# MCU.net
KiCad netlist of a schematic drawn in Altium Designer
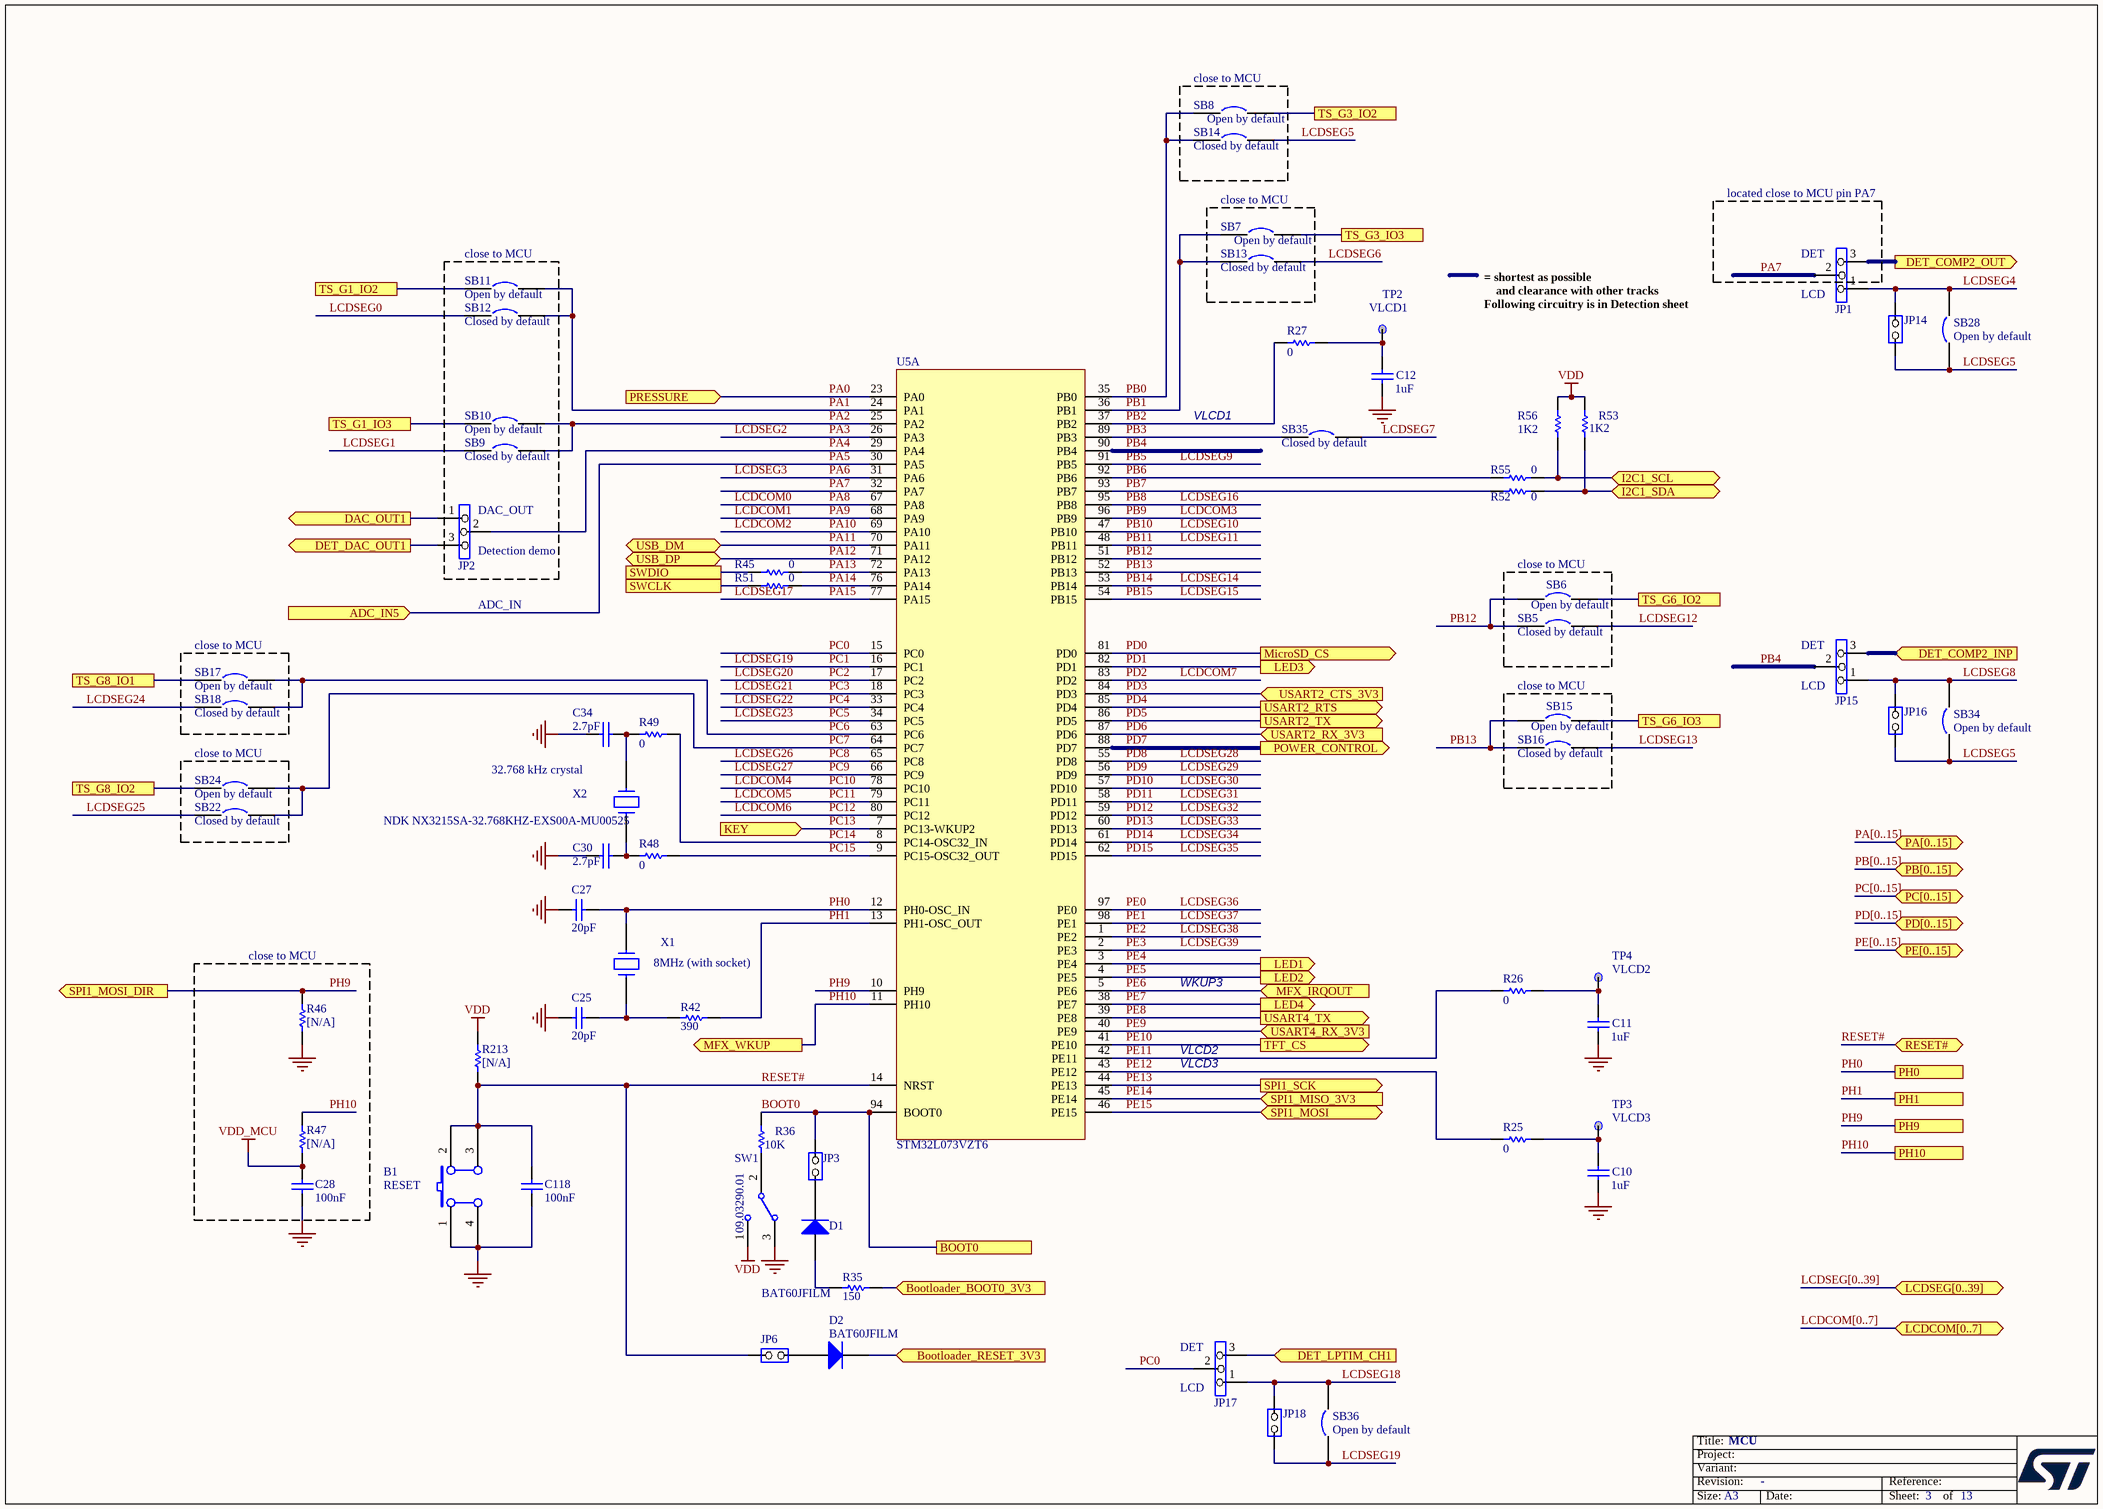
[diagram p0: MCU.SchDoc]

(export (version "E")
  (design (tool "Eeschema 10.0.6"))
  (components
    (comp (ref "B1")
      (value "RESET")
      (footprint "PB10")
      (description "SE PUSHBUTTON")
      (libsource (lib "Documents") (part "SW PUSHBUTTON"))
    )
    (comp (ref "C10")
      (value "1uF")
      (footprint "0603C")
      (description "Capacitor")
      (fields (field (name "PUBLISHER") "Altium Limited"))
      (libsource (lib "Miscellaneous Devices") (part "CAP"))
    )
    (comp (ref "C11")
      (value "1uF")
      (footprint "0603C")
      (description "Capacitor")
      (fields (field (name "PUBLISHER") "Altium Limited"))
      (libsource (lib "Miscellaneous Devices") (part "CAP"))
    )
    (comp (ref "C12")
      (value "1uF")
      (footprint "0603C")
      (description "Capacitor")
      (fields (field (name "PUBLISHER") "Altium Limited"))
      (libsource (lib "Miscellaneous Devices") (part "CAP"))
    )
    (comp (ref "C25")
      (value "20pF")
      (footprint "0402C")
      (description "Capacitor")
      (fields (field (name "PUBLISHER") "Altium Limited"))
      (libsource (lib "Miscellaneous Devices") (part "CAP"))
    )
    (comp (ref "C27")
      (value "20pF")
      (footprint "0402C")
      (description "Capacitor")
      (fields (field (name "PUBLISHER") "Altium Limited"))
      (libsource (lib "Miscellaneous Devices") (part "CAP"))
    )
    (comp (ref "C28")
      (value "100nF")
      (footprint "0402C")
      (description "Capacitor")
      (fields (field (name "PUBLISHER") "Altium Limited"))
      (libsource (lib "Miscellaneous Devices") (part "CAP"))
    )
    (comp (ref "C30")
      (value "2.7pF")
      (footprint "0603C")
      (description "Capacitor")
      (libsource (lib "*") (part "CAP"))
    )
    (comp (ref "C34")
      (value "2.7pF")
      (footprint "0603C")
      (description "Capacitor")
      (libsource (lib "*") (part "CAP"))
    )
    (comp (ref "C118")
      (value "100nF")
      (footprint "0402C")
      (description "Capacitor")
      (fields (field (name "PUBLISHER") "Altium Limited"))
      (libsource (lib "Miscellaneous Devices") (part "CAP"))
    )
    (comp (ref "D1")
      (value "BAT60JFILM")
      (footprint "SOD-323")
      (description "Default Diode")
      (fields (field (name "PUBLISHER") "Altium Limited"))
      (libsource (lib "Miscellaneous Devices") (part "Diode"))
    )
    (comp (ref "D2")
      (value "BAT60JFILM")
      (footprint "SOD-323")
      (description "Default Diode")
      (fields (field (name "PUBLISHER") "Altium Limited"))
      (libsource (lib "Miscellaneous Devices") (part "Diode"))
    )
    (comp (ref "JP1") (value "~") (footprint "SIP3") (libsource (lib "STR910_SCHLIB") (part "Jumper3")))
    (comp (ref "JP2") (value "~") (footprint "SIP3") (libsource (lib "STR910_SCHLIB") (part "Jumper3")))
    (comp (ref "JP3") (value "~") (footprint "SIP2") (libsource (lib "*") (part "JP2")))
    (comp (ref "JP6") (value "~") (footprint "SIP2") (libsource (lib "*") (part "JP2")))
    (comp (ref "JP14") (value "~") (footprint "SIP2") (libsource (lib "*") (part "JP2")))
    (comp (ref "JP15") (value "~") (footprint "SIP3") (libsource (lib "STR910_SCHLIB") (part "Jumper3")))
    (comp (ref "JP16") (value "~") (footprint "SIP2") (libsource (lib "*") (part "JP2")))
    (comp (ref "JP17") (value "~") (footprint "SIP3") (libsource (lib "STR910_SCHLIB") (part "Jumper3")))
    (comp (ref "JP18") (value "~") (footprint "SIP2") (libsource (lib "*") (part "JP2")))
    (comp (ref "R25")
      (value "0")
      (footprint "0603R")
      (description "Resistor")
      (fields (field (name "PUBLISHER") "Altium Limited"))
      (libsource (lib "Miscellaneous Devices") (part "Res1"))
    )
    (comp (ref "R26")
      (value "0")
      (footprint "0603R")
      (description "Resistor")
      (fields (field (name "PUBLISHER") "Altium Limited"))
      (libsource (lib "Miscellaneous Devices") (part "Res1"))
    )
    (comp (ref "R27")
      (value "0")
      (footprint "0603R")
      (description "Resistor")
      (fields (field (name "PUBLISHER") "Altium Limited"))
      (libsource (lib "Miscellaneous Devices") (part "Res1"))
    )
    (comp (ref "R35")
      (value "150")
      (footprint "0402R")
      (description "Resistor")
      (fields (field (name "PUBLISHER") "Altium Limited"))
      (libsource (lib "Miscellaneous Devices") (part "res1"))
    )
    (comp (ref "R36")
      (value "10K")
      (footprint "0402R")
      (description "Resistor")
      (fields (field (name "PUBLISHER") "Altium Limited"))
      (libsource (lib "Miscellaneous Devices") (part "res1"))
    )
    (comp (ref "R42")
      (value "390")
      (footprint "0603R")
      (description "Resistor")
      (fields (field (name "PUBLISHER") "Altium Limited"))
      (libsource (lib "Miscellaneous Devices") (part "Res1"))
    )
    (comp (ref "R45")
      (value "0")
      (footprint "0603R")
      (description "Resistor")
      (fields (field (name "PUBLISHER") "Altium Limited"))
      (libsource (lib "Miscellaneous Devices") (part "Res1"))
    )
    (comp (ref "R46")
      (value "[N/A]")
      (footprint "0603R")
      (description "Resistor")
      (fields (field (name "PUBLISHER") "Altium Limited"))
      (libsource (lib "Miscellaneous Devices") (part "res1"))
    )
    (comp (ref "R47")
      (value "[N/A]")
      (footprint "0603R")
      (description "Resistor")
      (fields (field (name "PUBLISHER") "Altium Limited"))
      (libsource (lib "Miscellaneous Devices") (part "res1"))
    )
    (comp (ref "R48")
      (value "0")
      (footprint "0603R")
      (description "Resistor")
      (fields (field (name "PUBLISHER") "Altium Limited"))
      (libsource (lib "") (part "Res1_1"))
    )
    (comp (ref "R49")
      (value "0")
      (footprint "0603R")
      (description "Resistor")
      (fields (field (name "PUBLISHER") "Altium Limited"))
      (libsource (lib "") (part "Res1_1"))
    )
    (comp (ref "R51")
      (value "0")
      (footprint "0603R")
      (description "Resistor")
      (fields (field (name "PUBLISHER") "Altium Limited"))
      (libsource (lib "Miscellaneous Devices") (part "Res1"))
    )
    (comp (ref "R52")
      (value "0")
      (footprint "0603R")
      (description "Resistor")
      (fields (field (name "PUBLISHER") "Altium Limited"))
      (libsource (lib "Miscellaneous Devices") (part "Res1"))
    )
    (comp (ref "R53")
      (value "1K2")
      (footprint "0603R")
      (description "Resistor")
      (fields (field (name "PUBLISHER") "Altium Limited"))
      (libsource (lib "Miscellaneous Devices") (part "Res1"))
    )
    (comp (ref "R55")
      (value "0")
      (footprint "0603R")
      (description "Resistor")
      (fields (field (name "PUBLISHER") "Altium Limited"))
      (libsource (lib "Miscellaneous Devices") (part "Res1"))
    )
    (comp (ref "R56")
      (value "1K2")
      (footprint "0603R")
      (description "Resistor")
      (fields (field (name "PUBLISHER") "Altium Limited"))
      (libsource (lib "Miscellaneous Devices") (part "Res1"))
    )
    (comp (ref "R213")
      (value "[N/A]")
      (footprint "0603R")
      (description "Resistor")
      (fields (field (name "PUBLISHER") "Altium Limited"))
      (libsource (lib "Miscellaneous Devices") (part "res1"))
    )
    (comp (ref "SB5")
      (value "Closed by default")
      (footprint "SB_0603")
      (description "Circuit Breaker")
      (fields (field (name "PUBLISHER") "Altium Limited"))
      (libsource (lib "Miscellaneous Devices") (part "Circuit Breaker"))
    )
    (comp (ref "SB6")
      (value "Open by default")
      (footprint "SB_0603")
      (description "Circuit Breaker")
      (fields (field (name "PUBLISHER") "Altium Limited"))
      (libsource (lib "Miscellaneous Devices") (part "Circuit Breaker"))
    )
    (comp (ref "SB7")
      (value "Open by default")
      (footprint "SB_0603")
      (description "Circuit Breaker")
      (fields (field (name "PUBLISHER") "Altium Limited"))
      (libsource (lib "Miscellaneous Devices") (part "Circuit Breaker"))
    )
    (comp (ref "SB8")
      (value "Open by default")
      (footprint "SB_0603")
      (description "Circuit Breaker")
      (fields (field (name "PUBLISHER") "Altium Limited"))
      (libsource (lib "Miscellaneous Devices") (part "Circuit Breaker"))
    )
    (comp (ref "SB9")
      (value "Closed by default")
      (footprint "SB_0603")
      (description "Circuit Breaker")
      (fields (field (name "PUBLISHER") "Altium Limited"))
      (libsource (lib "Miscellaneous Devices") (part "Circuit Breaker"))
    )
    (comp (ref "SB10")
      (value "Open by default")
      (footprint "SB_0603")
      (description "Circuit Breaker")
      (fields (field (name "PUBLISHER") "Altium Limited"))
      (libsource (lib "Miscellaneous Devices") (part "Circuit Breaker"))
    )
    (comp (ref "SB11")
      (value "Open by default")
      (footprint "SB_0603")
      (description "Circuit Breaker")
      (fields (field (name "PUBLISHER") "Altium Limited"))
      (libsource (lib "Miscellaneous Devices") (part "Circuit Breaker"))
    )
    (comp (ref "SB12")
      (value "Closed by default")
      (footprint "SB_0603")
      (description "Circuit Breaker")
      (fields (field (name "PUBLISHER") "Altium Limited"))
      (libsource (lib "Miscellaneous Devices") (part "Circuit Breaker"))
    )
    (comp (ref "SB13")
      (value "Closed by default")
      (footprint "SB_0603")
      (description "Circuit Breaker")
      (fields (field (name "PUBLISHER") "Altium Limited"))
      (libsource (lib "Miscellaneous Devices") (part "Circuit Breaker"))
    )
    (comp (ref "SB14")
      (value "Closed by default")
      (footprint "SB_0603")
      (description "Circuit Breaker")
      (fields (field (name "PUBLISHER") "Altium Limited"))
      (libsource (lib "Miscellaneous Devices") (part "Circuit Breaker"))
    )
    (comp (ref "SB15")
      (value "Open by default")
      (footprint "SB_0603")
      (description "Circuit Breaker")
      (fields (field (name "PUBLISHER") "Altium Limited"))
      (libsource (lib "Miscellaneous Devices") (part "Circuit Breaker"))
    )
    (comp (ref "SB16")
      (value "Closed by default")
      (footprint "SB_0603")
      (description "Circuit Breaker")
      (fields (field (name "PUBLISHER") "Altium Limited"))
      (libsource (lib "Miscellaneous Devices") (part "Circuit Breaker"))
    )
    (comp (ref "SB17")
      (value "Open by default")
      (footprint "SB_0603")
      (description "Circuit Breaker")
      (fields (field (name "PUBLISHER") "Altium Limited"))
      (libsource (lib "Miscellaneous Devices") (part "Circuit Breaker"))
    )
    (comp (ref "SB18")
      (value "Closed by default")
      (footprint "SB_0603")
      (description "Circuit Breaker")
      (fields (field (name "PUBLISHER") "Altium Limited"))
      (libsource (lib "Miscellaneous Devices") (part "Circuit Breaker"))
    )
    (comp (ref "SB22")
      (value "Closed by default")
      (footprint "SB_0603")
      (description "Circuit Breaker")
      (fields (field (name "PUBLISHER") "Altium Limited"))
      (libsource (lib "Miscellaneous Devices") (part "Circuit Breaker"))
    )
    (comp (ref "SB24")
      (value "Open by default")
      (footprint "SB_0603")
      (description "Circuit Breaker")
      (fields (field (name "PUBLISHER") "Altium Limited"))
      (libsource (lib "Miscellaneous Devices") (part "Circuit Breaker"))
    )
    (comp (ref "SB28")
      (value "Open by default")
      (footprint "SB_0603")
      (description "Circuit Breaker")
      (fields (field (name "PUBLISHER") "Altium Limited"))
      (libsource (lib "Miscellaneous Devices") (part "Circuit Breaker"))
    )
    (comp (ref "SB34")
      (value "Open by default")
      (footprint "SB_0603")
      (description "Circuit Breaker")
      (fields (field (name "PUBLISHER") "Altium Limited"))
      (libsource (lib "Miscellaneous Devices") (part "Circuit Breaker"))
    )
    (comp (ref "SB35")
      (value "Closed by default")
      (footprint "SB_0603")
      (description "Circuit Breaker")
      (fields (field (name "PUBLISHER") "Altium Limited"))
      (libsource (lib "Miscellaneous Devices") (part "Circuit Breaker"))
    )
    (comp (ref "SB36")
      (value "Open by default")
      (footprint "SB_0603")
      (description "Circuit Breaker")
      (fields (field (name "PUBLISHER") "Altium Limited"))
      (libsource (lib "Miscellaneous Devices") (part "Circuit Breaker"))
    )
    (comp (ref "SW1")
      (value "09.03290.01")
      (footprint "SW1_3TH_2R54_10X2R5")
      (description "SPDT Subminiature Toggle Switch, Right Angle Mounting, Vertical Actuation")
      (fields (field (name "PUBLISHER") "Altium Limited"))
      (libsource (lib "Miscellaneous Devices") (part "SW-SPDT"))
    )
    (comp (ref "TP2")
      (value "TP")
      (footprint "TP")
      (fields (field (name "SILKSCREEN") "VLCD1"))
      (libsource (lib "*") (part "TP"))
    )
    (comp (ref "TP3")
      (value "TP")
      (footprint "TP")
      (fields (field (name "SILKSCREEN") "VLCD3"))
      (libsource (lib "*") (part "TP"))
    )
    (comp (ref "TP4")
      (value "TP")
      (footprint "TP")
      (fields (field (name "SILKSCREEN") "VLCD2"))
      (libsource (lib "*") (part "TP"))
    )
    (comp (ref "U5")
      (value "STM32L073VZT6")
      (footprint "IC149_100_025_B5")
      (libsource (lib "Almos") (part "BigNemo"))
    )
    (comp (ref "X1")
      (value "8MHz (with socket)")
      (footprint "XTAL_SOCKET")
      (description "Crystal")
      (libsource (lib "*") (part "CRYSTAL"))
    )
    (comp (ref "X2")
      (value "NDK NX3215SA-32.768KHZ-EXS00A-MU00525")
      (footprint "XTAL_2SM_3R2X1R5")
      (description "Crystal")
      (libsource (lib "MB1167") (part "CRYSTAL_32K"))
    )
  )
  (nets
    (net (code "1") (name "/BOOT0") (class "Default")
      (node (ref "JP3") (pin "1") (pinfunction "COMMON_1") (pintype "passive"))
      (node (ref "R36") (pin "1") (pinfunction "1_1") (pintype "passive"))
      (node (ref "U5") (pin "94") (pinfunction "BOOT0_94") (pintype "passive"))
    )
    (net (code "2") (name "/Bootloader_BOOT0_3V3") (class "Default")
      (node (ref "R35") (pin "2") (pinfunction "2_2") (pintype "passive"))
    )
    (net (code "3") (name "/Bootloader_RESET_3V3") (class "Default")
      (node (ref "D2") (pin "2") (pinfunction "K_2") (pintype "passive"))
    )
    (net (code "4") (name "/DAC_OUT1") (class "Default") (node (ref "JP2") (pin "1") (pintype "passive")))
    (net (code "5") (name "/DET_COMP2_INP") (class "Default")
      (node (ref "JP15") (pin "3") (pintype "passive"))
    )
    (net (code "6") (name "/DET_COMP2_OUT") (class "Default")
      (node (ref "JP1") (pin "3") (pintype "passive"))
    )
    (net (code "7") (name "/DET_DAC_OUT1") (class "Default") (node (ref "JP2") (pin "3") (pintype "passive")))
    (net (code "8") (name "/DET_LPTIM_CH1") (class "Default")
      (node (ref "JP17") (pin "3") (pintype "passive"))
    )
    (net (code "9") (name "/I2C1_SCL") (class "Default")
      (node (ref "R55") (pin "2") (pinfunction "2_2") (pintype "passive"))
      (node (ref "R56") (pin "1") (pinfunction "1_1") (pintype "passive"))
    )
    (net (code "10") (name "/I2C1_SDA") (class "Default")
      (node (ref "R52") (pin "2") (pinfunction "2_2") (pintype "passive"))
      (node (ref "R53") (pin "1") (pinfunction "1_1") (pintype "passive"))
    )
    (net (code "12") (name "/LCDSEG0") (class "Default")
      (node (ref "SB12") (pin "1") (pinfunction "1_1") (pintype "passive"))
    )
    (net (code "13") (name "/LCDSEG1") (class "Default")
      (node (ref "SB9") (pin "1") (pinfunction "1_1") (pintype "passive"))
    )
    (net (code "14") (name "/LCDSEG4") (class "Default")
      (node (ref "JP1") (pin "1") (pintype "passive"))
      (node (ref "JP14") (pin "2") (pinfunction "NO_2") (pintype "passive"))
      (node (ref "SB28") (pin "2") (pinfunction "2_2") (pintype "passive"))
    )
    (net (code "15") (name "/LCDSEG5") (class "Default")
      (node (ref "JP14") (pin "1") (pinfunction "COMMON_1") (pintype "passive"))
      (node (ref "JP16") (pin "1") (pinfunction "COMMON_1") (pintype "passive"))
      (node (ref "SB14") (pin "2") (pinfunction "2_2") (pintype "passive"))
      (node (ref "SB28") (pin "1") (pinfunction "1_1") (pintype "passive"))
      (node (ref "SB34") (pin "1") (pinfunction "1_1") (pintype "passive"))
    )
    (net (code "16") (name "/LCDSEG6") (class "Default")
      (node (ref "SB13") (pin "2") (pinfunction "2_2") (pintype "passive"))
    )
    (net (code "17") (name "/LCDSEG7") (class "Default")
      (node (ref "SB35") (pin "2") (pinfunction "2_2") (pintype "passive"))
    )
    (net (code "18") (name "/LCDSEG8") (class "Default")
      (node (ref "JP15") (pin "1") (pintype "passive"))
      (node (ref "JP16") (pin "2") (pinfunction "NO_2") (pintype "passive"))
      (node (ref "SB34") (pin "2") (pinfunction "2_2") (pintype "passive"))
    )
    (net (code "19") (name "/LCDSEG12") (class "Default")
      (node (ref "SB5") (pin "2") (pinfunction "2_2") (pintype "passive"))
    )
    (net (code "20") (name "/LCDSEG13") (class "Default")
      (node (ref "SB16") (pin "2") (pinfunction "2_2") (pintype "passive"))
    )
    (net (code "21") (name "/LCDSEG18") (class "Default")
      (node (ref "JP17") (pin "1") (pintype "passive"))
      (node (ref "JP18") (pin "2") (pinfunction "NO_2") (pintype "passive"))
      (node (ref "SB36") (pin "2") (pinfunction "2_2") (pintype "passive"))
    )
    (net (code "22") (name "/LCDSEG24") (class "Default")
      (node (ref "SB18") (pin "1") (pinfunction "1_1") (pintype "passive"))
    )
    (net (code "23") (name "/LCDSEG25") (class "Default")
      (node (ref "SB22") (pin "1") (pinfunction "1_1") (pintype "passive"))
    )
    (net (code "25") (name "/PA0") (class "Default")
      (node (ref "U5") (pin "23") (pinfunction "PA0_23") (pintype "passive"))
    )
    (net (code "26") (name "/PA1") (class "Default")
      (node (ref "SB11") (pin "2") (pinfunction "2_2") (pintype "passive"))
      (node (ref "SB12") (pin "2") (pinfunction "2_2") (pintype "passive"))
      (node (ref "U5") (pin "24") (pinfunction "PA1_24") (pintype "passive"))
    )
    (net (code "27") (name "/PA2") (class "Default")
      (node (ref "SB10") (pin "2") (pinfunction "2_2") (pintype "passive"))
      (node (ref "SB9") (pin "2") (pinfunction "2_2") (pintype "passive"))
      (node (ref "U5") (pin "25") (pinfunction "PA2_25") (pintype "passive"))
    )
    (net (code "28") (name "/PA3") (class "Default")
      (node (ref "U5") (pin "26") (pinfunction "PA3_26") (pintype "passive"))
    )
    (net (code "29") (name "/PA4") (class "Default")
      (node (ref "JP2") (pin "2") (pintype "passive"))
      (node (ref "U5") (pin "29") (pinfunction "PA4_29") (pintype "passive"))
    )
    (net (code "30") (name "/PA5") (class "Default")
      (node (ref "U5") (pin "30") (pinfunction "PA5_30") (pintype "passive"))
    )
    (net (code "31") (name "/PA6") (class "Default")
      (node (ref "U5") (pin "31") (pinfunction "PA6_31") (pintype "passive"))
    )
    (net (code "32") (name "/PA7") (class "Default")
      (node (ref "JP1") (pin "2") (pintype "passive"))
      (node (ref "U5") (pin "32") (pinfunction "PA7_32") (pintype "passive"))
    )
    (net (code "33") (name "/PA8") (class "Default")
      (node (ref "U5") (pin "67") (pinfunction "PA8_67") (pintype "passive"))
    )
    (net (code "34") (name "/PA9") (class "Default")
      (node (ref "U5") (pin "68") (pinfunction "PA9_68") (pintype "passive"))
    )
    (net (code "35") (name "/PA10") (class "Default")
      (node (ref "U5") (pin "69") (pinfunction "PA10_69") (pintype "passive"))
    )
    (net (code "36") (name "/PA11") (class "Default")
      (node (ref "U5") (pin "70") (pinfunction "PA11_70") (pintype "passive"))
    )
    (net (code "37") (name "/PA12") (class "Default")
      (node (ref "U5") (pin "71") (pinfunction "PA12_71") (pintype "passive"))
    )
    (net (code "38") (name "/PA13") (class "Default")
      (node (ref "R45") (pin "2") (pinfunction "2_2") (pintype "passive"))
      (node (ref "U5") (pin "72") (pinfunction "PA13_72") (pintype "passive"))
    )
    (net (code "39") (name "/PA14") (class "Default")
      (node (ref "R51") (pin "2") (pinfunction "2_2") (pintype "passive"))
      (node (ref "U5") (pin "76") (pinfunction "PA14_76") (pintype "passive"))
    )
    (net (code "40") (name "/PA15") (class "Default")
      (node (ref "U5") (pin "77") (pinfunction "PA15_77") (pintype "passive"))
    )
    (net (code "42") (name "/PB0") (class "Default")
      (node (ref "SB14") (pin "1") (pinfunction "1_1") (pintype "passive"))
      (node (ref "SB8") (pin "1") (pinfunction "1_1") (pintype "passive"))
      (node (ref "U5") (pin "35") (pinfunction "PB0_35") (pintype "passive"))
    )
    (net (code "43") (name "/PB1") (class "Default")
      (node (ref "SB13") (pin "1") (pinfunction "1_1") (pintype "passive"))
      (node (ref "SB7") (pin "1") (pinfunction "1_1") (pintype "passive"))
      (node (ref "U5") (pin "36") (pinfunction "PB1_36") (pintype "passive"))
    )
    (net (code "44") (name "/PB2") (class "Default")
      (node (ref "R27") (pin "1") (pinfunction "1_1") (pintype "passive"))
      (node (ref "U5") (pin "37") (pinfunction "PB2_37") (pintype "passive"))
    )
    (net (code "45") (name "/PB3") (class "Default")
      (node (ref "SB35") (pin "1") (pinfunction "1_1") (pintype "passive"))
      (node (ref "U5") (pin "89") (pinfunction "PB3_89") (pintype "passive"))
    )
    (net (code "46") (name "/PB4") (class "Default")
      (node (ref "JP15") (pin "2") (pintype "passive"))
      (node (ref "U5") (pin "90") (pinfunction "PB4_90") (pintype "passive"))
    )
    (net (code "47") (name "/PB5") (class "Default")
      (node (ref "U5") (pin "91") (pinfunction "PB5_91") (pintype "passive"))
    )
    (net (code "48") (name "/PB6") (class "Default")
      (node (ref "R55") (pin "1") (pinfunction "1_1") (pintype "passive"))
      (node (ref "U5") (pin "92") (pinfunction "PB6_92") (pintype "passive"))
    )
    (net (code "49") (name "/PB7") (class "Default")
      (node (ref "R52") (pin "1") (pinfunction "1_1") (pintype "passive"))
      (node (ref "U5") (pin "93") (pinfunction "PB7_93") (pintype "passive"))
    )
    (net (code "50") (name "/PB8") (class "Default")
      (node (ref "U5") (pin "95") (pinfunction "PB8_95") (pintype "passive"))
    )
    (net (code "51") (name "/PB9") (class "Default")
      (node (ref "U5") (pin "96") (pinfunction "PB9_96") (pintype "passive"))
    )
    (net (code "52") (name "/PB10") (class "Default")
      (node (ref "U5") (pin "47") (pinfunction "PB10_47") (pintype "passive"))
    )
    (net (code "53") (name "/PB11") (class "Default")
      (node (ref "U5") (pin "48") (pinfunction "PB11_48") (pintype "passive"))
    )
    (net (code "54") (name "/PB12") (class "Default")
      (node (ref "SB5") (pin "1") (pinfunction "1_1") (pintype "passive"))
      (node (ref "SB6") (pin "1") (pinfunction "1_1") (pintype "passive"))
      (node (ref "U5") (pin "51") (pinfunction "PB12_51") (pintype "passive"))
    )
    (net (code "55") (name "/PB13") (class "Default")
      (node (ref "SB15") (pin "1") (pinfunction "1_1") (pintype "passive"))
      (node (ref "SB16") (pin "1") (pinfunction "1_1") (pintype "passive"))
      (node (ref "U5") (pin "52") (pinfunction "PB13_52") (pintype "passive"))
    )
    (net (code "56") (name "/PB14") (class "Default")
      (node (ref "U5") (pin "53") (pinfunction "PB14_53") (pintype "passive"))
    )
    (net (code "57") (name "/PB15") (class "Default")
      (node (ref "U5") (pin "54") (pinfunction "PB15_54") (pintype "passive"))
    )
    (net (code "59") (name "/PC0") (class "Default")
      (node (ref "JP17") (pin "2") (pintype "passive"))
      (node (ref "U5") (pin "15") (pinfunction "PC0_15") (pintype "passive"))
    )
    (net (code "60") (name "/PC1") (class "Default")
      (node (ref "JP18") (pin "1") (pinfunction "COMMON_1") (pintype "passive"))
      (node (ref "SB36") (pin "1") (pinfunction "1_1") (pintype "passive"))
      (node (ref "U5") (pin "16") (pinfunction "PC1_16") (pintype "passive"))
    )
    (net (code "61") (name "/PC2") (class "Default")
      (node (ref "U5") (pin "17") (pinfunction "PC2_17") (pintype "passive"))
    )
    (net (code "62") (name "/PC3") (class "Default")
      (node (ref "U5") (pin "18") (pinfunction "PC3_18") (pintype "passive"))
    )
    (net (code "63") (name "/PC4") (class "Default")
      (node (ref "U5") (pin "33") (pinfunction "PC4_33") (pintype "passive"))
    )
    (net (code "64") (name "/PC5") (class "Default")
      (node (ref "U5") (pin "34") (pinfunction "PC5_34") (pintype "passive"))
    )
    (net (code "65") (name "/PC6") (class "Default")
      (node (ref "SB17") (pin "2") (pinfunction "2_2") (pintype "passive"))
      (node (ref "SB18") (pin "2") (pinfunction "2_2") (pintype "passive"))
      (node (ref "U5") (pin "63") (pinfunction "PC6_63") (pintype "passive"))
    )
    (net (code "66") (name "/PC7") (class "Default")
      (node (ref "SB22") (pin "2") (pinfunction "2_2") (pintype "passive"))
      (node (ref "SB24") (pin "2") (pinfunction "2_2") (pintype "passive"))
      (node (ref "U5") (pin "64") (pinfunction "PC7_64") (pintype "passive"))
    )
    (net (code "67") (name "/PC8") (class "Default")
      (node (ref "U5") (pin "65") (pinfunction "PC8_65") (pintype "passive"))
    )
    (net (code "68") (name "/PC9") (class "Default")
      (node (ref "U5") (pin "66") (pinfunction "PC9_66") (pintype "passive"))
    )
    (net (code "69") (name "/PC10") (class "Default")
      (node (ref "U5") (pin "78") (pinfunction "PC10_78") (pintype "passive"))
    )
    (net (code "70") (name "/PC11") (class "Default")
      (node (ref "U5") (pin "79") (pinfunction "PC11_79") (pintype "passive"))
    )
    (net (code "71") (name "/PC12") (class "Default")
      (node (ref "U5") (pin "80") (pinfunction "PC12_80") (pintype "passive"))
    )
    (net (code "72") (name "/PC13") (class "Default")
      (node (ref "U5") (pin "7") (pinfunction "PC13-WKUP2_7") (pintype "passive"))
    )
    (net (code "73") (name "/PC14") (class "Default")
      (node (ref "R49") (pin "2") (pinfunction "2_2") (pintype "passive"))
      (node (ref "U5") (pin "8") (pinfunction "PC14-OSC32_IN_8") (pintype "passive"))
    )
    (net (code "74") (name "/PC15") (class "Default")
      (node (ref "R48") (pin "2") (pinfunction "2_2") (pintype "passive"))
      (node (ref "U5") (pin "9") (pinfunction "PC15-OSC32_OUT_9") (pintype "passive"))
    )
    (net (code "76") (name "/PD0") (class "Default")
      (node (ref "U5") (pin "81") (pinfunction "PD0_81") (pintype "passive"))
    )
    (net (code "77") (name "/PD1") (class "Default")
      (node (ref "U5") (pin "82") (pinfunction "PD1_82") (pintype "passive"))
    )
    (net (code "78") (name "/PD2") (class "Default")
      (node (ref "U5") (pin "83") (pinfunction "PD2_83") (pintype "passive"))
    )
    (net (code "79") (name "/PD3") (class "Default")
      (node (ref "U5") (pin "84") (pinfunction "PD3_84") (pintype "passive"))
    )
    (net (code "80") (name "/PD4") (class "Default")
      (node (ref "U5") (pin "85") (pinfunction "PD4_85") (pintype "passive"))
    )
    (net (code "81") (name "/PD5") (class "Default")
      (node (ref "U5") (pin "86") (pinfunction "PD5_86") (pintype "passive"))
    )
    (net (code "82") (name "/PD6") (class "Default")
      (node (ref "U5") (pin "87") (pinfunction "PD6_87") (pintype "passive"))
    )
    (net (code "83") (name "/PD7") (class "Default")
      (node (ref "U5") (pin "88") (pinfunction "PD7_88") (pintype "passive"))
    )
    (net (code "84") (name "/PD8") (class "Default")
      (node (ref "U5") (pin "55") (pinfunction "PD8_55") (pintype "passive"))
    )
    (net (code "85") (name "/PD9") (class "Default")
      (node (ref "U5") (pin "56") (pinfunction "PD9_56") (pintype "passive"))
    )
    (net (code "86") (name "/PD10") (class "Default")
      (node (ref "U5") (pin "57") (pinfunction "PD10_57") (pintype "passive"))
    )
    (net (code "87") (name "/PD11") (class "Default")
      (node (ref "U5") (pin "58") (pinfunction "PD11_58") (pintype "passive"))
    )
    (net (code "88") (name "/PD12") (class "Default")
      (node (ref "U5") (pin "59") (pinfunction "PD12_59") (pintype "passive"))
    )
    (net (code "89") (name "/PD13") (class "Default")
      (node (ref "U5") (pin "60") (pinfunction "PD13_60") (pintype "passive"))
    )
    (net (code "90") (name "/PD14") (class "Default")
      (node (ref "U5") (pin "61") (pinfunction "PD14_61") (pintype "passive"))
    )
    (net (code "91") (name "/PD15") (class "Default")
      (node (ref "U5") (pin "62") (pinfunction "PD15_62") (pintype "passive"))
    )
    (net (code "93") (name "/PE0") (class "Default")
      (node (ref "U5") (pin "97") (pinfunction "PE0_97") (pintype "passive"))
    )
    (net (code "94") (name "/PE1") (class "Default")
      (node (ref "U5") (pin "98") (pinfunction "PE1_98") (pintype "passive"))
    )
    (net (code "95") (name "/PE2") (class "Default")
      (node (ref "U5") (pin "1") (pinfunction "PE2_1") (pintype "passive"))
    )
    (net (code "96") (name "/PE3") (class "Default")
      (node (ref "U5") (pin "2") (pinfunction "PE3_2") (pintype "passive"))
    )
    (net (code "97") (name "/PE4") (class "Default")
      (node (ref "U5") (pin "3") (pinfunction "PE4_3") (pintype "passive"))
    )
    (net (code "98") (name "/PE5") (class "Default")
      (node (ref "U5") (pin "4") (pinfunction "PE5_4") (pintype "passive"))
    )
    (net (code "99") (name "/PE6") (class "Default")
      (node (ref "U5") (pin "5") (pinfunction "PE6_5") (pintype "passive"))
    )
    (net (code "100") (name "/PE7") (class "Default")
      (node (ref "U5") (pin "38") (pinfunction "PE7_38") (pintype "passive"))
    )
    (net (code "101") (name "/PE8") (class "Default")
      (node (ref "U5") (pin "39") (pinfunction "PE8_39") (pintype "passive"))
    )
    (net (code "102") (name "/PE9") (class "Default")
      (node (ref "U5") (pin "40") (pinfunction "PE9_40") (pintype "passive"))
    )
    (net (code "103") (name "/PE10") (class "Default")
      (node (ref "U5") (pin "41") (pinfunction "PE10_41") (pintype "passive"))
    )
    (net (code "104") (name "/PE11") (class "Default")
      (node (ref "R26") (pin "1") (pinfunction "1_1") (pintype "passive"))
      (node (ref "U5") (pin "42") (pinfunction "PE11_42") (pintype "passive"))
    )
    (net (code "105") (name "/PE12") (class "Default")
      (node (ref "R25") (pin "1") (pinfunction "1_1") (pintype "passive"))
      (node (ref "U5") (pin "43") (pinfunction "PE12_43") (pintype "passive"))
    )
    (net (code "106") (name "/PE13") (class "Default")
      (node (ref "U5") (pin "44") (pinfunction "PE13_44") (pintype "passive"))
    )
    (net (code "107") (name "/PE14") (class "Default")
      (node (ref "U5") (pin "45") (pinfunction "PE14_45") (pintype "passive"))
    )
    (net (code "108") (name "/PE15") (class "Default")
      (node (ref "U5") (pin "46") (pinfunction "PE15_46") (pintype "passive"))
    )
    (net (code "110") (name "/PH0") (class "Default")
      (node (ref "C27") (pin "1") (pinfunction "1_1") (pintype "passive"))
      (node (ref "U5") (pin "12") (pinfunction "PH0-OSC_IN_12") (pintype "passive"))
      (node (ref "X1") (pin "2") (pinfunction "2_2") (pintype "passive"))
    )
    (net (code "111") (name "/PH1") (class "Default")
      (node (ref "R42") (pin "1") (pinfunction "1_1") (pintype "passive"))
      (node (ref "U5") (pin "13") (pinfunction "PH1-OSC_OUT_13") (pintype "passive"))
    )
    (net (code "112") (name "/PH9") (class "Default")
      (node (ref "R46") (pin "2") (pinfunction "2_2") (pintype "passive"))
      (node (ref "U5") (pin "10") (pinfunction "PH9_10") (pintype "passive"))
    )
    (net (code "113") (name "/PH10") (class "Default")
      (node (ref "R47") (pin "2") (pinfunction "2_2") (pintype "passive"))
      (node (ref "U5") (pin "11") (pinfunction "PH10_11") (pintype "passive"))
    )
    (net (code "114") (name "/RESET#") (class "Default")
      (node (ref "B1") (pin "2") (pinfunction "B0_2") (pintype "passive"))
      (node (ref "B1") (pin "3") (pinfunction "B1_3") (pintype "passive"))
      (node (ref "C118") (pin "2") (pinfunction "2_2") (pintype "passive"))
      (node (ref "JP6") (pin "1") (pinfunction "COMMON_1") (pintype "passive"))
      (node (ref "R213") (pin "1") (pinfunction "1_1") (pintype "passive"))
      (node (ref "U5") (pin "14") (pinfunction "NRST_14") (pintype "passive"))
    )
    (net (code "115") (name "/SWCLK") (class "Default")
      (node (ref "R51") (pin "1") (pinfunction "1_1") (pintype "passive"))
    )
    (net (code "116") (name "/SWDIO") (class "Default")
      (node (ref "R45") (pin "1") (pinfunction "1_1") (pintype "passive"))
    )
    (net (code "117") (name "/TS_G1_IO2") (class "Default")
      (node (ref "SB11") (pin "1") (pinfunction "1_1") (pintype "passive"))
    )
    (net (code "118") (name "/TS_G1_IO3") (class "Default")
      (node (ref "SB10") (pin "1") (pinfunction "1_1") (pintype "passive"))
    )
    (net (code "119") (name "/TS_G3_IO2") (class "Default")
      (node (ref "SB8") (pin "2") (pinfunction "2_2") (pintype "passive"))
    )
    (net (code "120") (name "/TS_G3_IO3") (class "Default")
      (node (ref "SB7") (pin "2") (pinfunction "2_2") (pintype "passive"))
    )
    (net (code "121") (name "/TS_G6_IO2") (class "Default")
      (node (ref "SB6") (pin "2") (pinfunction "2_2") (pintype "passive"))
    )
    (net (code "122") (name "/TS_G6_IO3") (class "Default")
      (node (ref "SB15") (pin "2") (pinfunction "2_2") (pintype "passive"))
    )
    (net (code "123") (name "/TS_G8_IO1") (class "Default")
      (node (ref "SB17") (pin "1") (pinfunction "1_1") (pintype "passive"))
    )
    (net (code "124") (name "/TS_G8_IO2") (class "Default")
      (node (ref "SB24") (pin "1") (pinfunction "1_1") (pintype "passive"))
    )
    (net (code "125") (name "GND") (class "Default")
      (node (ref "B1") (pin "1") (pinfunction "A0_1") (pintype "passive"))
      (node (ref "B1") (pin "4") (pinfunction "A1_4") (pintype "passive"))
      (node (ref "C10") (pin "1") (pinfunction "1_1") (pintype "passive"))
      (node (ref "C11") (pin "1") (pinfunction "1_1") (pintype "passive"))
      (node (ref "C118") (pin "1") (pinfunction "1_1") (pintype "passive"))
      (node (ref "C12") (pin "1") (pinfunction "1_1") (pintype "passive"))
      (node (ref "C25") (pin "2") (pinfunction "2_2") (pintype "passive"))
      (node (ref "C27") (pin "2") (pinfunction "2_2") (pintype "passive"))
      (node (ref "C28") (pin "1") (pinfunction "1_1") (pintype "passive"))
      (node (ref "C30") (pin "2") (pinfunction "2_2") (pintype "passive"))
      (node (ref "C34") (pin "2") (pinfunction "2_2") (pintype "passive"))
      (node (ref "R46") (pin "1") (pinfunction "1_1") (pintype "passive"))
      (node (ref "SW1") (pin "3") (pintype "passive"))
    )
    (net (code "126") (name "Net-(C10-Pad2)") (class "Default")
      (node (ref "C10") (pin "2") (pinfunction "2_2") (pintype "passive"))
      (node (ref "R25") (pin "2") (pinfunction "2_2") (pintype "passive"))
      (node (ref "TP3") (pin "1") (pinfunction "1_1") (pintype "passive"))
    )
    (net (code "127") (name "Net-(C11-Pad2)") (class "Default")
      (node (ref "C11") (pin "2") (pinfunction "2_2") (pintype "passive"))
      (node (ref "R26") (pin "2") (pinfunction "2_2") (pintype "passive"))
      (node (ref "TP4") (pin "1") (pinfunction "1_1") (pintype "passive"))
    )
    (net (code "128") (name "Net-(C12-Pad2)") (class "Default")
      (node (ref "C12") (pin "2") (pinfunction "2_2") (pintype "passive"))
      (node (ref "R27") (pin "2") (pinfunction "2_2") (pintype "passive"))
      (node (ref "TP2") (pin "1") (pinfunction "1_1") (pintype "passive"))
    )
    (net (code "129") (name "Net-(C25-Pad1)") (class "Default")
      (node (ref "C25") (pin "1") (pinfunction "1_1") (pintype "passive"))
      (node (ref "R42") (pin "2") (pinfunction "2_2") (pintype "passive"))
      (node (ref "X1") (pin "1") (pinfunction "1_1") (pintype "passive"))
    )
    (net (code "130") (name "Net-(C30-Pad1)") (class "Default")
      (node (ref "C30") (pin "1") (pinfunction "1_1") (pintype "passive"))
      (node (ref "R48") (pin "1") (pinfunction "1_1") (pintype "passive"))
      (node (ref "X2") (pin "1") (pinfunction "1_1") (pintype "passive"))
    )
    (net (code "131") (name "Net-(C34-Pad1)") (class "Default")
      (node (ref "C34") (pin "1") (pinfunction "1_1") (pintype "passive"))
      (node (ref "R49") (pin "1") (pinfunction "1_1") (pintype "passive"))
      (node (ref "X2") (pin "2") (pinfunction "2_2") (pintype "passive"))
    )
    (net (code "132") (name "Net-(D1-A)") (class "Default")
      (node (ref "D1") (pin "1") (pinfunction "A_1") (pintype "passive"))
      (node (ref "R35") (pin "1") (pinfunction "1_1") (pintype "passive"))
    )
    (net (code "133") (name "Net-(D1-K)") (class "Default")
      (node (ref "D1") (pin "2") (pinfunction "K_2") (pintype "passive"))
      (node (ref "JP3") (pin "2") (pinfunction "NO_2") (pintype "passive"))
    )
    (net (code "134") (name "Net-(D2-A)") (class "Default")
      (node (ref "D2") (pin "1") (pinfunction "A_1") (pintype "passive"))
      (node (ref "JP6") (pin "2") (pinfunction "NO_2") (pintype "passive"))
    )
    (net (code "135") (name "Net-(R36-Pad2)") (class "Default")
      (node (ref "R36") (pin "2") (pinfunction "2_2") (pintype "passive"))
      (node (ref "SW1") (pin "2") (pintype "passive"))
    )
    (net (code "136") (name "VDD") (class "Default")
      (node (ref "R213") (pin "2") (pinfunction "2_2") (pintype "passive"))
      (node (ref "R53") (pin "2") (pinfunction "2_2") (pintype "passive"))
      (node (ref "R56") (pin "2") (pinfunction "2_2") (pintype "passive"))
      (node (ref "SW1") (pin "1") (pintype "passive"))
    )
    (net (code "137") (name "VDD_MCU") (class "Default")
      (node (ref "C28") (pin "2") (pinfunction "2_2") (pintype "passive"))
      (node (ref "R47") (pin "1") (pinfunction "1_1") (pintype "passive"))
    )
  )
)
